# Sheet2.net
KiCad netlist of a schematic drawn in Altium Designer
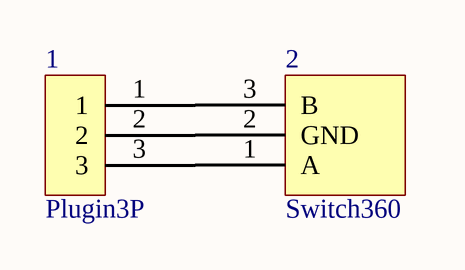
[diagram p0: Sheet2.SchDoc]

(export (version "E")
  (design (tool "Eeschema 10.0.6"))
  (components
    (comp (ref "1") (value "Plugin3P") (footprint "Plugin3P") (libsource (lib "Schlib1") (part "Plugin3P")))
    (comp (ref "2")
      (value "Switch360")
      (footprint "Switch360")
      (libsource (lib "Schlib1") (part "Switch360"))
    )
  )
  (nets
    (net (code "1") (name "Net-(2-A)") (class "Default")
      (node (ref "1") (pin "3") (pinfunction "3_3") (pintype "passive"))
      (node (ref "2") (pin "1") (pinfunction "A_1") (pintype "passive"))
    )
    (net (code "2") (name "Net-(2-B)") (class "Default")
      (node (ref "1") (pin "1") (pinfunction "1_1") (pintype "passive"))
      (node (ref "2") (pin "3") (pinfunction "B_3") (pintype "passive"))
    )
    (net (code "3") (name "Net-(2-GND)") (class "Default")
      (node (ref "1") (pin "2") (pinfunction "2_2") (pintype "passive"))
      (node (ref "2") (pin "2") (pinfunction "GND_2") (pintype "passive"))
    )
  )
)
